# euromap.net
KiCad netlist of a schematic drawn in Altium Designer
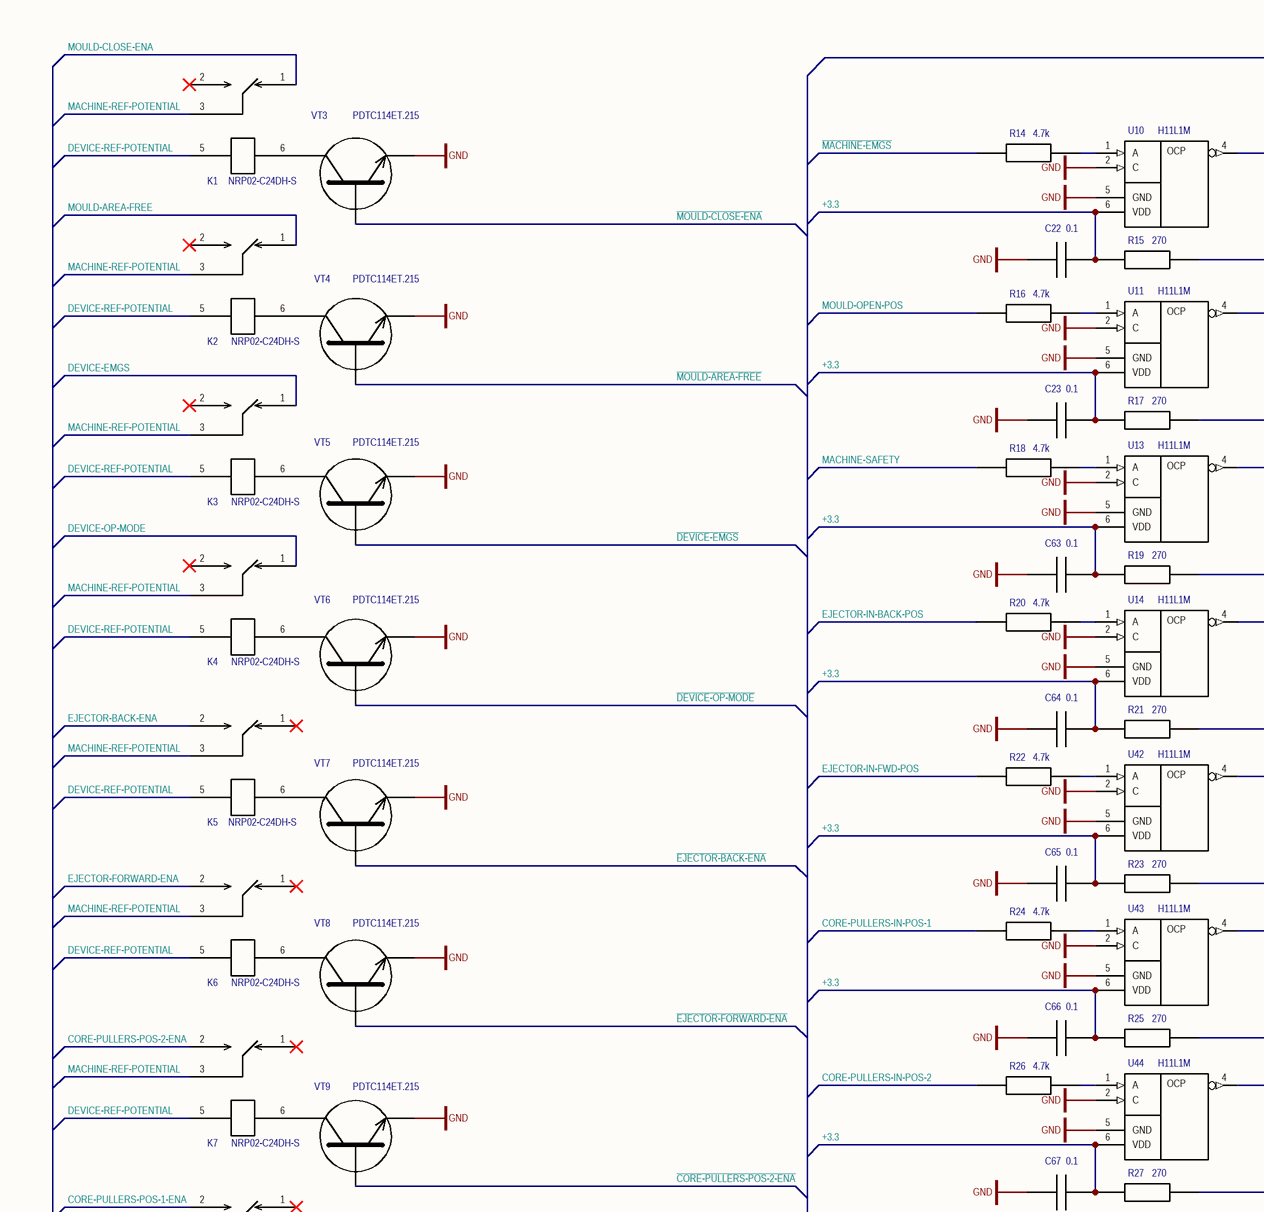
[diagram p0: euromap.SchDoc, top left]
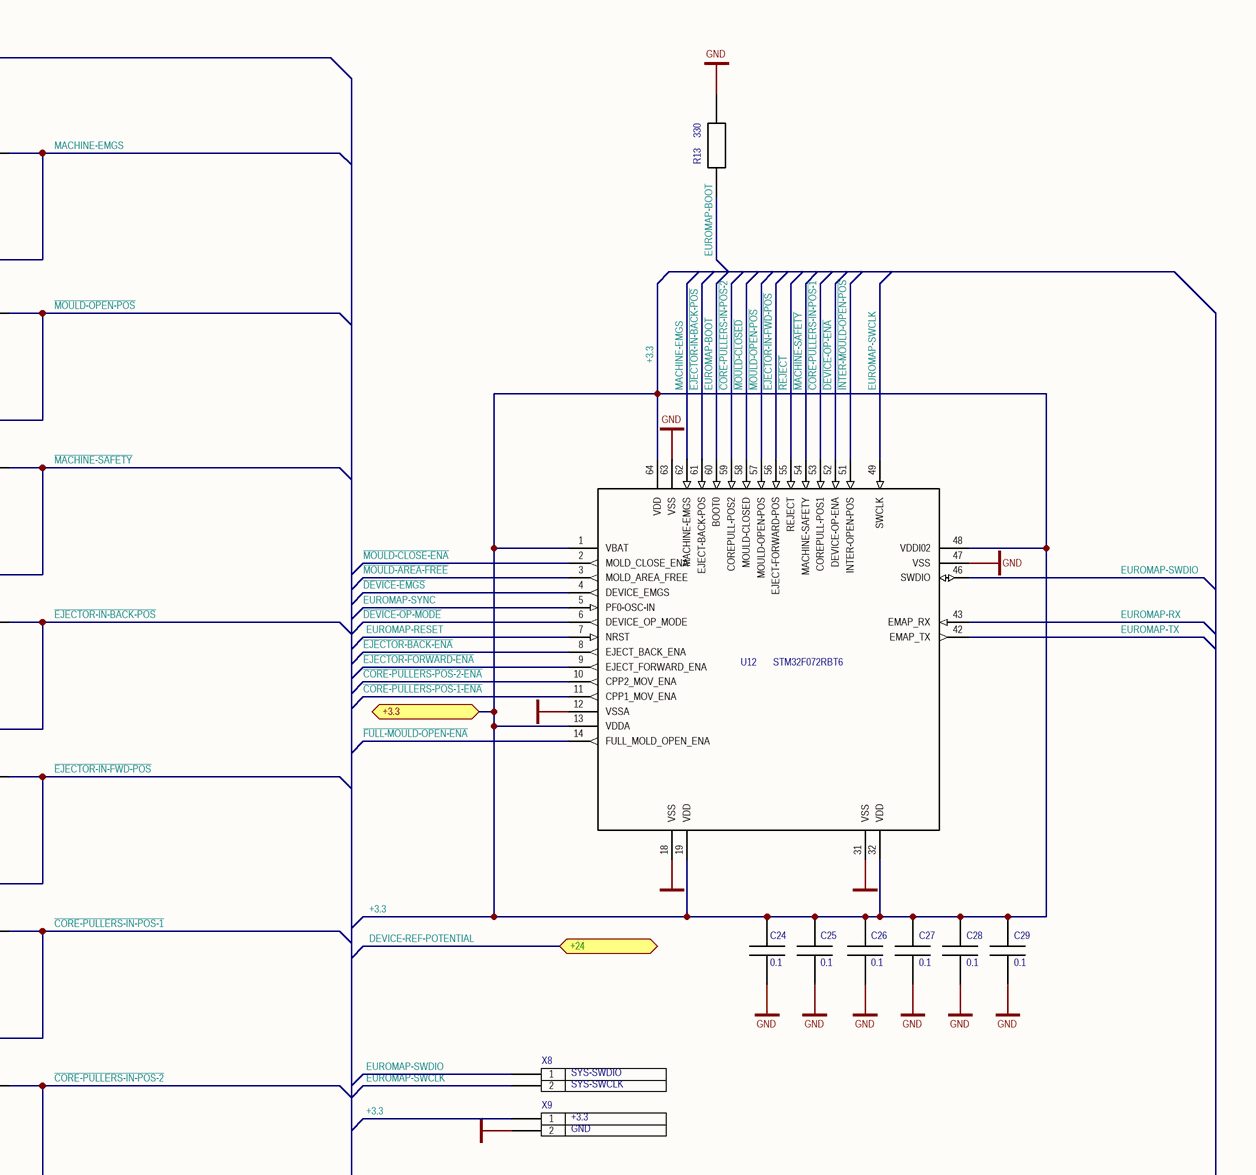
[diagram p1: euromap.SchDoc, top right]
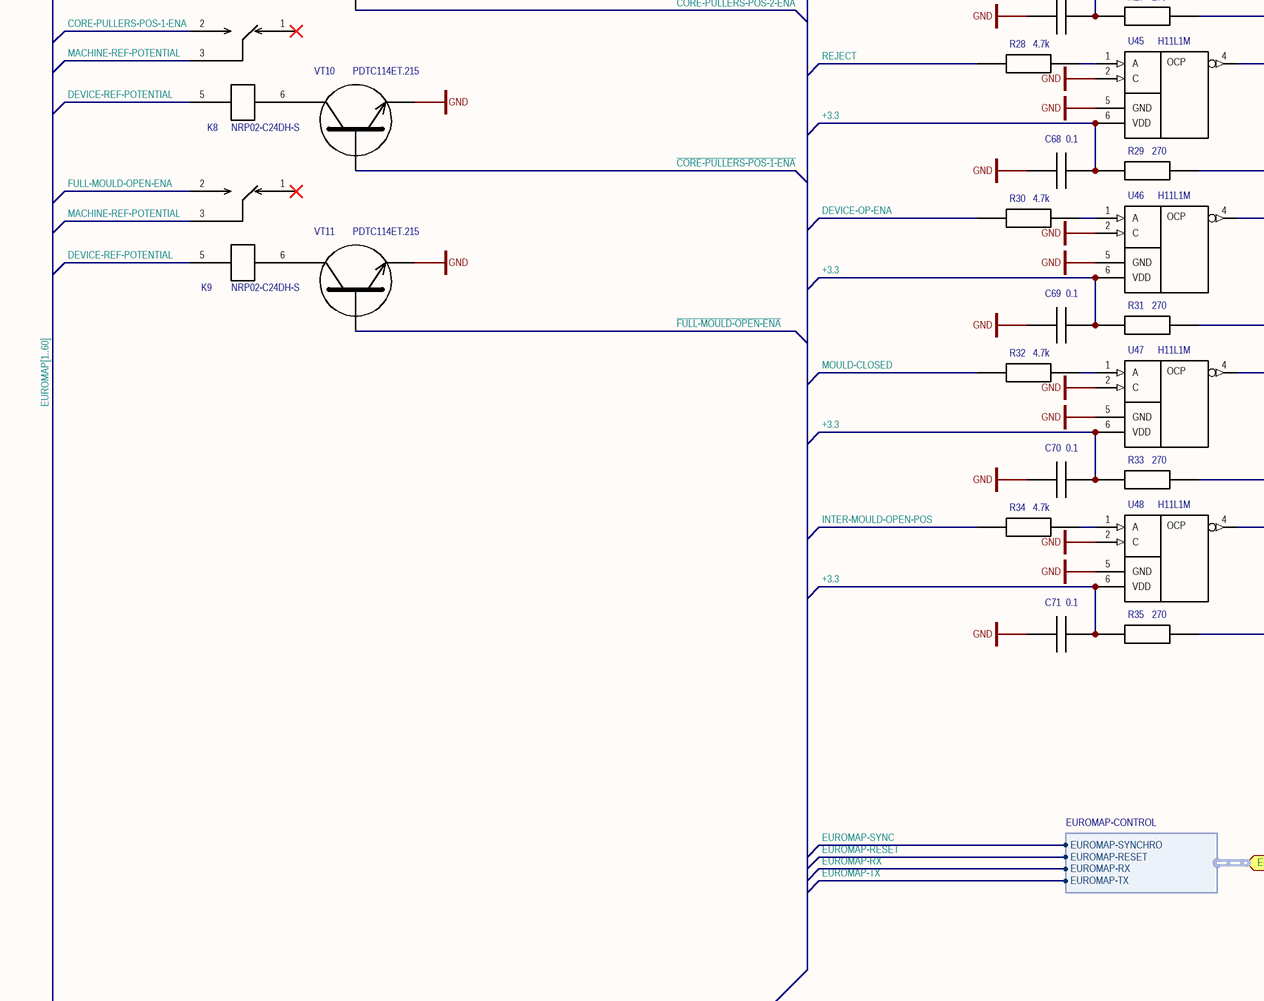
[diagram p2: euromap.SchDoc, bottom left]
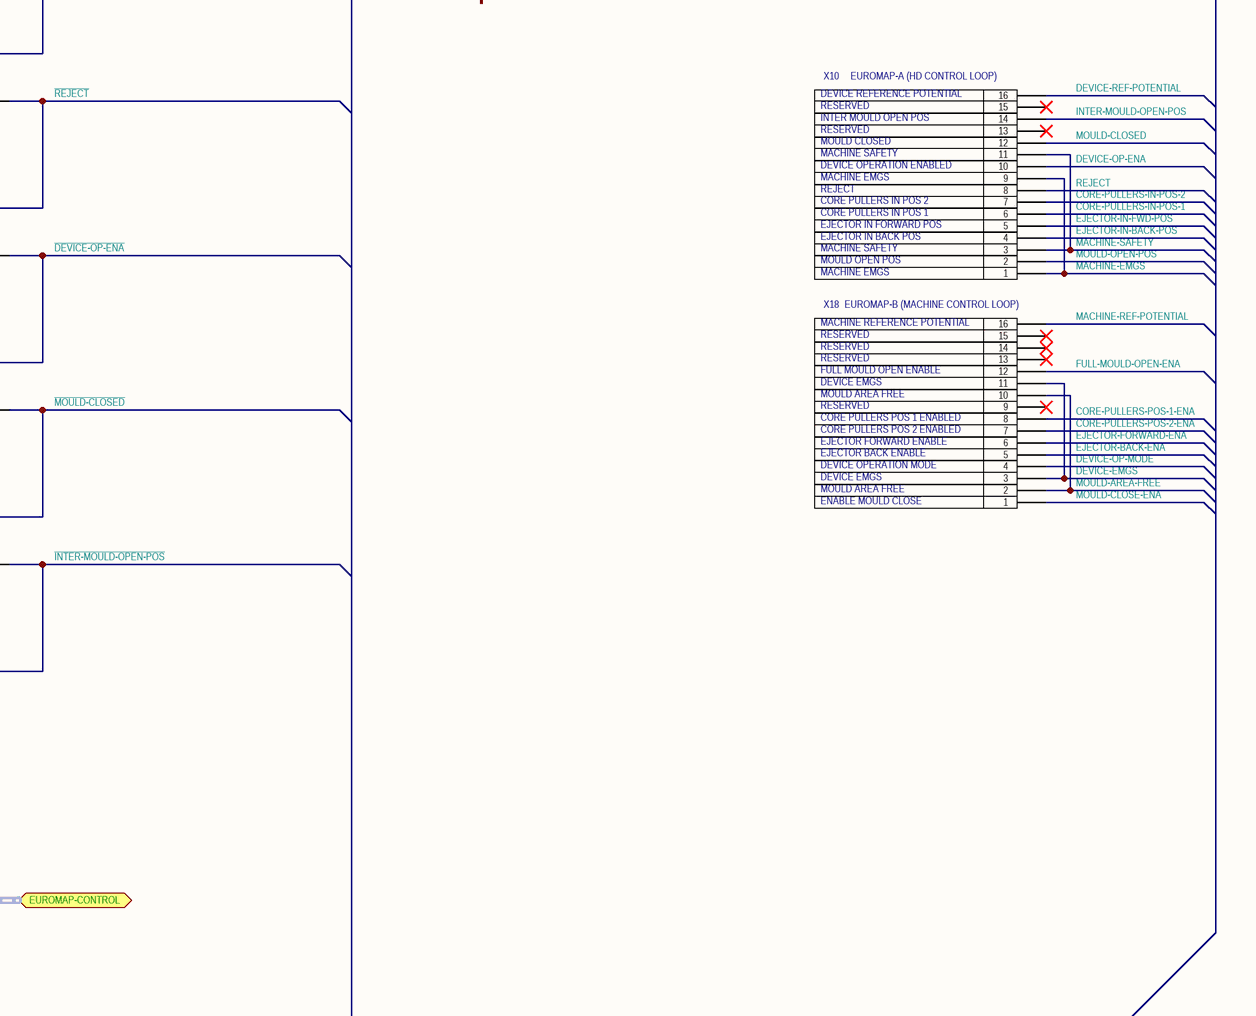
[diagram p3: euromap.SchDoc, bottom right]

(export (version "E")
  (design (tool "Eeschema 10.0.6"))
  (components
    (comp (ref "C22")
      (value "0.1")
      (footprint "CAPC2012X04N")
      (description "SMD конденсатор")
      (libsource (lib "ulysses_library") (part "C"))
    )
    (comp (ref "C23")
      (value "0.1")
      (footprint "CAPC2012X04N")
      (description "SMD конденсатор")
      (libsource (lib "ulysses_library") (part "C"))
    )
    (comp (ref "C24")
      (value "0.1")
      (footprint "CAPC1608X05N")
      (description "SMD конденсатор")
      (libsource (lib "ulysses_library") (part "C"))
    )
    (comp (ref "C25")
      (value "0.1")
      (footprint "CAPC1608X05N")
      (description "SMD конденсатор")
      (libsource (lib "ulysses_library") (part "C"))
    )
    (comp (ref "C26")
      (value "0.1")
      (footprint "CAPC1608X05N")
      (description "SMD конденсатор")
      (libsource (lib "ulysses_library") (part "C"))
    )
    (comp (ref "C27")
      (value "0.1")
      (footprint "CAPC1608X05N")
      (description "SMD конденсатор")
      (libsource (lib "ulysses_library") (part "C"))
    )
    (comp (ref "C28")
      (value "0.1")
      (footprint "CAPC1608X05N")
      (description "SMD конденсатор")
      (libsource (lib "ulysses_library") (part "C"))
    )
    (comp (ref "C29")
      (value "0.1")
      (footprint "CAPC1608X05N")
      (description "SMD конденсатор")
      (libsource (lib "ulysses_library") (part "C"))
    )
    (comp (ref "C63")
      (value "0.1")
      (footprint "CAPC2012X04N")
      (description "SMD конденсатор")
      (libsource (lib "ulysses_library") (part "C"))
    )
    (comp (ref "C64")
      (value "0.1")
      (footprint "CAPC2012X04N")
      (description "SMD конденсатор")
      (libsource (lib "ulysses_library") (part "C"))
    )
    (comp (ref "C65")
      (value "0.1")
      (footprint "CAPC2012X04N")
      (description "SMD конденсатор")
      (libsource (lib "ulysses_library") (part "C"))
    )
    (comp (ref "C66")
      (value "0.1")
      (footprint "CAPC2012X04N")
      (description "SMD конденсатор")
      (libsource (lib "ulysses_library") (part "C"))
    )
    (comp (ref "C67")
      (value "0.1")
      (footprint "CAPC2012X04N")
      (description "SMD конденсатор")
      (libsource (lib "ulysses_library") (part "C"))
    )
    (comp (ref "C68")
      (value "0.1")
      (footprint "CAPC2012X04N")
      (description "SMD конденсатор")
      (libsource (lib "ulysses_library") (part "C"))
    )
    (comp (ref "C69")
      (value "0.1")
      (footprint "CAPC2012X04N")
      (description "SMD конденсатор")
      (libsource (lib "ulysses_library") (part "C"))
    )
    (comp (ref "C70")
      (value "0.1")
      (footprint "CAPC2012X04N")
      (description "SMD конденсатор")
      (libsource (lib "ulysses_library") (part "C"))
    )
    (comp (ref "C71")
      (value "0.1")
      (footprint "CAPC2012X04N")
      (description "SMD конденсатор")
      (libsource (lib "ulysses_library") (part "C"))
    )
    (comp (ref "K1")
      (value "NRP02-C24DH-S")
      (footprint "R_NRP02")
      (description "Электромеханическое реле")
      (libsource (lib "ulysses_library") (part "NRP02-C24DH-S"))
    )
    (comp (ref "K2")
      (value "NRP02-C24DH-S")
      (footprint "R_NRP02")
      (description "Электромеханическое реле")
      (libsource (lib "ulysses_library") (part "NRP02-C24DH-S"))
    )
    (comp (ref "K3")
      (value "NRP02-C24DH-S")
      (footprint "R_NRP02")
      (description "Электромеханическое реле")
      (libsource (lib "ulysses_library") (part "NRP02-C24DH-S"))
    )
    (comp (ref "K4")
      (value "NRP02-C24DH-S")
      (footprint "R_NRP02")
      (description "Электромеханическое реле")
      (libsource (lib "ulysses_library") (part "NRP02-C24DH-S"))
    )
    (comp (ref "K5")
      (value "NRP02-C24DH-S")
      (footprint "R_NRP02")
      (description "Электромеханическое реле")
      (libsource (lib "") (part "NRP02-C24DH-S_1"))
    )
    (comp (ref "K6")
      (value "NRP02-C24DH-S")
      (footprint "R_NRP02")
      (description "Электромеханическое реле")
      (libsource (lib "ulysses_library") (part "NRP02-C24DH-S"))
    )
    (comp (ref "K7")
      (value "NRP02-C24DH-S")
      (footprint "R_NRP02")
      (description "Электромеханическое реле")
      (libsource (lib "ulysses_library") (part "NRP02-C24DH-S"))
    )
    (comp (ref "K8")
      (value "NRP02-C24DH-S")
      (footprint "R_NRP02")
      (description "Электромеханическое реле")
      (libsource (lib "ulysses_library") (part "NRP02-C24DH-S"))
    )
    (comp (ref "K9")
      (value "NRP02-C24DH-S")
      (footprint "R_NRP02")
      (description "Электромеханическое реле")
      (libsource (lib "ulysses_library") (part "NRP02-C24DH-S"))
    )
    (comp (ref "R13")
      (value "330")
      (footprint "RESC1608X05N")
      (description "SMD резистор")
      (libsource (lib "ulysses_library") (part "R"))
    )
    (comp (ref "R14")
      (value "4.7k")
      (footprint "RESC2012X04N")
      (description "SMD резистор")
      (libsource (lib "ulysses_library") (part "R"))
    )
    (comp (ref "R15")
      (value "270")
      (footprint "RESC2012X04N")
      (description "SMD резистор")
      (libsource (lib "ulysses_library") (part "R"))
    )
    (comp (ref "R16")
      (value "4.7k")
      (footprint "RESC2012X04N")
      (description "SMD резистор")
      (libsource (lib "ulysses_library") (part "R"))
    )
    (comp (ref "R17")
      (value "270")
      (footprint "RESC2012X04N")
      (description "SMD резистор")
      (libsource (lib "ulysses_library") (part "R"))
    )
    (comp (ref "R18")
      (value "4.7k")
      (footprint "RESC2012X04N")
      (description "SMD резистор")
      (libsource (lib "ulysses_library") (part "R"))
    )
    (comp (ref "R19")
      (value "270")
      (footprint "RESC2012X04N")
      (description "SMD резистор")
      (libsource (lib "ulysses_library") (part "R"))
    )
    (comp (ref "R20")
      (value "4.7k")
      (footprint "RESC2012X04N")
      (description "SMD резистор")
      (libsource (lib "ulysses_library") (part "R"))
    )
    (comp (ref "R21")
      (value "270")
      (footprint "RESC2012X04N")
      (description "SMD резистор")
      (libsource (lib "ulysses_library") (part "R"))
    )
    (comp (ref "R22")
      (value "4.7k")
      (footprint "RESC2012X04N")
      (description "SMD резистор")
      (libsource (lib "ulysses_library") (part "R"))
    )
    (comp (ref "R23")
      (value "270")
      (footprint "RESC2012X04N")
      (description "SMD резистор")
      (libsource (lib "ulysses_library") (part "R"))
    )
    (comp (ref "R24")
      (value "4.7k")
      (footprint "RESC2012X04N")
      (description "SMD резистор")
      (libsource (lib "ulysses_library") (part "R"))
    )
    (comp (ref "R25")
      (value "270")
      (footprint "RESC2012X04N")
      (description "SMD резистор")
      (libsource (lib "ulysses_library") (part "R"))
    )
    (comp (ref "R26")
      (value "4.7k")
      (footprint "RESC2012X04N")
      (description "SMD резистор")
      (libsource (lib "ulysses_library") (part "R"))
    )
    (comp (ref "R27")
      (value "270")
      (footprint "RESC2012X04N")
      (description "SMD резистор")
      (libsource (lib "ulysses_library") (part "R"))
    )
    (comp (ref "R28")
      (value "4.7k")
      (footprint "RESC2012X04N")
      (description "SMD резистор")
      (libsource (lib "ulysses_library") (part "R"))
    )
    (comp (ref "R29")
      (value "270")
      (footprint "RESC2012X04N")
      (description "SMD резистор")
      (libsource (lib "ulysses_library") (part "R"))
    )
    (comp (ref "R30")
      (value "4.7k")
      (footprint "RESC2012X04N")
      (description "SMD резистор")
      (libsource (lib "ulysses_library") (part "R"))
    )
    (comp (ref "R31")
      (value "270")
      (footprint "RESC2012X04N")
      (description "SMD резистор")
      (libsource (lib "ulysses_library") (part "R"))
    )
    (comp (ref "R32")
      (value "4.7k")
      (footprint "RESC2012X04N")
      (description "SMD резистор")
      (libsource (lib "ulysses_library") (part "R"))
    )
    (comp (ref "R33")
      (value "270")
      (footprint "RESC2012X04N")
      (description "SMD резистор")
      (libsource (lib "ulysses_library") (part "R"))
    )
    (comp (ref "R34")
      (value "4.7k")
      (footprint "RESC2012X04N")
      (description "SMD резистор")
      (libsource (lib "ulysses_library") (part "R"))
    )
    (comp (ref "R35")
      (value "270")
      (footprint "RESC2012X04N")
      (description "SMD резистор")
      (libsource (lib "ulysses_library") (part "R"))
    )
    (comp (ref "U10")
      (value "H11L1M")
      (footprint "DIP6")
      (description "Fairchild H11L1M Schmitt Trigger Output Optocoupler")
      (libsource (lib "ulysses_library") (part "H11L1M"))
    )
    (comp (ref "U11")
      (value "H11L1M")
      (footprint "DIP6")
      (description "Fairchild H11L1M Schmitt Trigger Output Optocoupler")
      (libsource (lib "ulysses_library") (part "H11L1M"))
    )
    (comp (ref "U12")
      (value "STM32F072RBT6")
      (footprint "TSQFP50P1200X1200X160-64N")
      (description "Микроконтроллер")
      (libsource (lib "ulysses_library") (part "STM32F072RBT6"))
    )
    (comp (ref "U13")
      (value "H11L1M")
      (footprint "DIP6")
      (description "Fairchild H11L1M Schmitt Trigger Output Optocoupler")
      (libsource (lib "ulysses_library") (part "H11L1M"))
    )
    (comp (ref "U14")
      (value "H11L1M")
      (footprint "DIP6")
      (description "Fairchild H11L1M Schmitt Trigger Output Optocoupler")
      (libsource (lib "ulysses_library") (part "H11L1M"))
    )
    (comp (ref "U42")
      (value "H11L1M")
      (footprint "DIP6")
      (description "Fairchild H11L1M Schmitt Trigger Output Optocoupler")
      (libsource (lib "") (part "H11L1M_1"))
    )
    (comp (ref "U43")
      (value "H11L1M")
      (footprint "DIP6")
      (description "Fairchild H11L1M Schmitt Trigger Output Optocoupler")
      (libsource (lib "ulysses_library") (part "H11L1M"))
    )
    (comp (ref "U44")
      (value "H11L1M")
      (footprint "DIP6")
      (description "Fairchild H11L1M Schmitt Trigger Output Optocoupler")
      (libsource (lib "ulysses_library") (part "H11L1M"))
    )
    (comp (ref "U45")
      (value "H11L1M")
      (footprint "DIP6")
      (description "Fairchild H11L1M Schmitt Trigger Output Optocoupler")
      (libsource (lib "ulysses_library") (part "H11L1M"))
    )
    (comp (ref "U46")
      (value "H11L1M")
      (footprint "DIP6")
      (description "Fairchild H11L1M Schmitt Trigger Output Optocoupler")
      (libsource (lib "ulysses_library") (part "H11L1M"))
    )
    (comp (ref "U47")
      (value "H11L1M")
      (footprint "DIP6")
      (description "Fairchild H11L1M Schmitt Trigger Output Optocoupler")
      (libsource (lib "ulysses_library") (part "H11L1M"))
    )
    (comp (ref "U48")
      (value "H11L1M")
      (footprint "DIP6")
      (description "Fairchild H11L1M Schmitt Trigger Output Optocoupler")
      (libsource (lib "ulysses_library") (part "H11L1M"))
    )
    (comp (ref "VT3")
      (value "PDTC114ET.215")
      (footprint "SOT95P238X102-3N")
      (description "NPN transistor with bias circuit")
      (libsource (lib "ulysses_library") (part "PDTC114ET.215"))
    )
    (comp (ref "VT4")
      (value "PDTC114ET.215")
      (footprint "SOT95P238X102-3N")
      (description "NPN transistor with bias circuit")
      (libsource (lib "ulysses_library") (part "PDTC114ET.215"))
    )
    (comp (ref "VT5")
      (value "PDTC114ET.215")
      (footprint "SOT95P238X102-3N")
      (description "NPN transistor with bias circuit")
      (libsource (lib "ulysses_library") (part "PDTC114ET.215"))
    )
    (comp (ref "VT6")
      (value "PDTC114ET.215")
      (footprint "SOT95P238X102-3N")
      (description "NPN transistor with bias circuit")
      (libsource (lib "ulysses_library") (part "PDTC114ET.215"))
    )
    (comp (ref "VT7")
      (value "PDTC114ET.215")
      (footprint "SOT95P238X102-3N")
      (description "NPN transistor with bias circuit")
      (libsource (lib "") (part "PDTC114ET.215_1"))
    )
    (comp (ref "VT8")
      (value "PDTC114ET.215")
      (footprint "SOT95P238X102-3N")
      (description "NPN transistor with bias circuit")
      (libsource (lib "ulysses_library") (part "PDTC114ET.215"))
    )
    (comp (ref "VT9")
      (value "PDTC114ET.215")
      (footprint "SOT95P238X102-3N")
      (description "NPN transistor with bias circuit")
      (libsource (lib "ulysses_library") (part "PDTC114ET.215"))
    )
    (comp (ref "VT10")
      (value "PDTC114ET.215")
      (footprint "SOT95P238X102-3N")
      (description "NPN transistor with bias circuit")
      (libsource (lib "ulysses_library") (part "PDTC114ET.215"))
    )
    (comp (ref "VT11")
      (value "PDTC114ET.215")
      (footprint "SOT95P238X102-3N")
      (description "NPN transistor with bias circuit")
      (libsource (lib "ulysses_library") (part "PDTC114ET.215"))
    )
    (comp (ref "X8")
      (value "Jamper ZL201")
      (footprint "ZL201-2")
      (libsource (lib "ulysses_library") (part "Jamper ZL201"))
    )
    (comp (ref "X9")
      (value "Jamper ZL201")
      (footprint "ZL201-2")
      (libsource (lib "ulysses_library") (part "Jamper ZL201"))
    )
    (comp (ref "X10")
      (value "EUROMAP-A (HD CONTROL LOOP)")
      (footprint "MINI-FIT-16-WAY-M")
      (libsource (lib "ulysses_library") (part "MINI-FIT-16-WAY-M"))
    )
    (comp (ref "X18")
      (value "EUROMAP-B (MACHINE CONTROL LOOP)")
      (footprint "MINI-FIT-16-WAY-M")
      (libsource (lib "ulysses_library") (part "MINI-FIT-16-WAY-M"))
    )
  )
  (nets
    (net (code "62") (name "/+3.3") (class "Default")
      (node (ref "C22") (pin "2") (pinfunction "2_2") (pintype "passive"))
      (node (ref "C23") (pin "2") (pinfunction "2_2") (pintype "passive"))
      (node (ref "C24") (pin "2") (pinfunction "2_2") (pintype "passive"))
      (node (ref "C25") (pin "2") (pinfunction "2_2") (pintype "passive"))
      (node (ref "C26") (pin "2") (pinfunction "2_2") (pintype "passive"))
      (node (ref "C27") (pin "2") (pinfunction "2_2") (pintype "passive"))
      (node (ref "C28") (pin "2") (pinfunction "2_2") (pintype "passive"))
      (node (ref "C29") (pin "2") (pinfunction "2_2") (pintype "passive"))
      (node (ref "C63") (pin "2") (pinfunction "2_2") (pintype "passive"))
      (node (ref "C64") (pin "2") (pinfunction "2_2") (pintype "passive"))
      (node (ref "C65") (pin "2") (pinfunction "2_2") (pintype "passive"))
      (node (ref "C66") (pin "2") (pinfunction "2_2") (pintype "passive"))
      (node (ref "C67") (pin "2") (pinfunction "2_2") (pintype "passive"))
      (node (ref "C68") (pin "2") (pinfunction "2_2") (pintype "passive"))
      (node (ref "C69") (pin "2") (pinfunction "2_2") (pintype "passive"))
      (node (ref "C70") (pin "2") (pinfunction "2_2") (pintype "passive"))
      (node (ref "C71") (pin "2") (pinfunction "2_2") (pintype "passive"))
      (node (ref "R15") (pin "1") (pintype "passive"))
      (node (ref "R17") (pin "1") (pintype "passive"))
      (node (ref "R19") (pin "1") (pintype "passive"))
      (node (ref "R21") (pin "1") (pintype "passive"))
      (node (ref "R23") (pin "1") (pintype "passive"))
      (node (ref "R25") (pin "1") (pintype "passive"))
      (node (ref "R27") (pin "1") (pintype "passive"))
      (node (ref "R29") (pin "1") (pintype "passive"))
      (node (ref "R31") (pin "1") (pintype "passive"))
      (node (ref "R33") (pin "1") (pintype "passive"))
      (node (ref "R35") (pin "1") (pintype "passive"))
      (node (ref "U10") (pin "6") (pinfunction "VDD_6") (pintype "power_in"))
      (node (ref "U11") (pin "6") (pinfunction "VDD_6") (pintype "power_in"))
      (node (ref "U12") (pin "1") (pinfunction "VBAT_1") (pintype "power_in"))
      (node (ref "U12") (pin "13") (pinfunction "VDDA_13") (pintype "power_in"))
      (node (ref "U12") (pin "19") (pinfunction "VDD_19") (pintype "power_in"))
      (node (ref "U12") (pin "32") (pinfunction "VDD_32") (pintype "power_in"))
      (node (ref "U12") (pin "48") (pinfunction "VDDI02_48") (pintype "power_in"))
      (node (ref "U12") (pin "64") (pinfunction "VDD_64") (pintype "power_in"))
      (node (ref "U13") (pin "6") (pinfunction "VDD_6") (pintype "power_in"))
      (node (ref "U14") (pin "6") (pinfunction "VDD_6") (pintype "power_in"))
      (node (ref "U42") (pin "6") (pinfunction "VDD_6") (pintype "power_in"))
      (node (ref "U43") (pin "6") (pinfunction "VDD_6") (pintype "power_in"))
      (node (ref "U44") (pin "6") (pinfunction "VDD_6") (pintype "power_in"))
      (node (ref "U45") (pin "6") (pinfunction "VDD_6") (pintype "power_in"))
      (node (ref "U46") (pin "6") (pinfunction "VDD_6") (pintype "power_in"))
      (node (ref "U47") (pin "6") (pinfunction "VDD_6") (pintype "power_in"))
      (node (ref "U48") (pin "6") (pinfunction "VDD_6") (pintype "power_in"))
      (node (ref "X9") (pin "1") (pinfunction "1_1") (pintype "passive"))
    )
    (net (code "63") (name "/CORE-PULLERS-IN-POS-1") (class "Default")
      (node (ref "R24") (pin "1") (pintype "passive"))
      (node (ref "X10") (pin "6") (pinfunction "6_6") (pintype "passive"))
    )
    (net (code "64") (name "/CORE-PULLERS-IN-POS-2") (class "Default")
      (node (ref "R26") (pin "1") (pintype "passive"))
      (node (ref "X10") (pin "7") (pinfunction "7_7") (pintype "passive"))
    )
    (net (code "65") (name "/CORE-PULLERS-POS-1-ENA") (class "Default")
      (node (ref "K8") (pin "2") (pinfunction "2_2") (pintype "passive"))
      (node (ref "X18") (pin "8") (pinfunction "8_8") (pintype "passive"))
    )
    (net (code "66") (name "/CORE-PULLERS-POS-2-ENA") (class "Default")
      (node (ref "K7") (pin "2") (pinfunction "2_2") (pintype "passive"))
      (node (ref "X18") (pin "7") (pinfunction "7_7") (pintype "passive"))
    )
    (net (code "67") (name "/DEVICE-EMGS") (class "Default")
      (node (ref "K3") (pin "1") (pinfunction "1_1") (pintype "passive"))
      (node (ref "X18") (pin "11") (pinfunction "11_11") (pintype "passive"))
      (node (ref "X18") (pin "3") (pinfunction "3_3") (pintype "passive"))
    )
    (net (code "68") (name "/DEVICE-OP-ENA") (class "Default")
      (node (ref "R30") (pin "1") (pintype "passive"))
      (node (ref "X10") (pin "10") (pinfunction "10_10") (pintype "passive"))
    )
    (net (code "69") (name "/DEVICE-OP-MODE") (class "Default")
      (node (ref "K4") (pin "1") (pinfunction "1_1") (pintype "passive"))
      (node (ref "X18") (pin "4") (pinfunction "4_4") (pintype "passive"))
    )
    (net (code "70") (name "/DEVICE-REF-POTENTIAL") (class "Default")
      (node (ref "K1") (pin "5") (pinfunction "5_5") (pintype "passive"))
      (node (ref "K2") (pin "5") (pinfunction "5_5") (pintype "passive"))
      (node (ref "K3") (pin "5") (pinfunction "5_5") (pintype "passive"))
      (node (ref "K4") (pin "5") (pinfunction "5_5") (pintype "passive"))
      (node (ref "K5") (pin "5") (pinfunction "5_5") (pintype "passive"))
      (node (ref "K6") (pin "5") (pinfunction "5_5") (pintype "passive"))
      (node (ref "K7") (pin "5") (pinfunction "5_5") (pintype "passive"))
      (node (ref "K8") (pin "5") (pinfunction "5_5") (pintype "passive"))
      (node (ref "K9") (pin "5") (pinfunction "5_5") (pintype "passive"))
      (node (ref "X10") (pin "16") (pinfunction "16_16") (pintype "passive"))
    )
    (net (code "71") (name "/EJECTOR-BACK-ENA") (class "Default")
      (node (ref "K5") (pin "2") (pinfunction "2_2") (pintype "passive"))
      (node (ref "X18") (pin "5") (pinfunction "5_5") (pintype "passive"))
    )
    (net (code "72") (name "/EJECTOR-FORWARD-ENA") (class "Default")
      (node (ref "K6") (pin "2") (pinfunction "2_2") (pintype "passive"))
      (node (ref "X18") (pin "6") (pinfunction "6_6") (pintype "passive"))
    )
    (net (code "73") (name "/EJECTOR-IN-BACK-POS") (class "Default")
      (node (ref "R20") (pin "1") (pintype "passive"))
      (node (ref "X10") (pin "4") (pinfunction "4_4") (pintype "passive"))
    )
    (net (code "74") (name "/EJECTOR-IN-FWD-POS") (class "Default")
      (node (ref "R22") (pin "1") (pintype "passive"))
      (node (ref "X10") (pin "5") (pinfunction "5_5") (pintype "passive"))
    )
    (net (code "75") (name "/EUROMAP-BOOT") (class "Default")
      (node (ref "R13") (pin "2") (pinfunction "2_2") (pintype "passive"))
      (node (ref "U12") (pin "60") (pinfunction "BOOT0_60") (pintype "input"))
    )
    (net (code "76") (name "/EUROMAP-RESET") (class "Default")
      (node (ref "U12") (pin "7") (pinfunction "NRST_7") (pintype "input"))
    )
    (net (code "77") (name "/EUROMAP-RX") (class "Default")
      (node (ref "U12") (pin "43") (pinfunction "EMAP_RX_43") (pintype "input"))
    )
    (net (code "78") (name "/EUROMAP-SWCLK") (class "Default")
      (node (ref "U12") (pin "49") (pinfunction "SWCLK_49") (pintype "input"))
      (node (ref "X8") (pin "2") (pinfunction "2_2") (pintype "passive"))
    )
    (net (code "79") (name "/EUROMAP-SWDIO") (class "Default")
      (node (ref "U12") (pin "46") (pinfunction "SWDIO_46") (pintype "bidirectional"))
      (node (ref "X8") (pin "1") (pinfunction "1_1") (pintype "passive"))
    )
    (net (code "80") (name "/EUROMAP-SYNC") (class "Default")
      (node (ref "U12") (pin "5") (pinfunction "PF0-OSC-IN_5") (pintype "input"))
    )
    (net (code "81") (name "/EUROMAP-TX") (class "Default")
      (node (ref "U12") (pin "42") (pinfunction "EMAP_TX_42") (pintype "output"))
    )
    (net (code "83") (name "/FULL-MOULD-OPEN-ENA") (class "Default")
      (node (ref "K9") (pin "2") (pinfunction "2_2") (pintype "passive"))
      (node (ref "X18") (pin "12") (pinfunction "12_12") (pintype "passive"))
    )
    (net (code "84") (name "/INTER-MOULD-OPEN-POS") (class "Default")
      (node (ref "R34") (pin "1") (pintype "passive"))
      (node (ref "X10") (pin "14") (pinfunction "14_14") (pintype "passive"))
    )
    (net (code "85") (name "/MACHINE-EMGS") (class "Default")
      (node (ref "R15") (pin "2") (pinfunction "2_2") (pintype "passive"))
      (node (ref "U10") (pin "4") (pinfunction "OUT_4") (pintype "output"))
      (node (ref "U12") (pin "62") (pinfunction "MACHINE-EMGS_62") (pintype "input"))
      (node (ref "X10") (pin "1") (pinfunction "1_1") (pintype "passive"))
      (node (ref "X10") (pin "9") (pinfunction "9_9") (pintype "passive"))
    )
    (net (code "86") (name "/MACHINE-REF-POTENTIAL") (class "Default")
      (node (ref "K1") (pin "3") (pinfunction "3_3") (pintype "passive"))
      (node (ref "K2") (pin "3") (pinfunction "3_3") (pintype "passive"))
      (node (ref "K3") (pin "3") (pinfunction "3_3") (pintype "passive"))
      (node (ref "K4") (pin "3") (pinfunction "3_3") (pintype "passive"))
      (node (ref "K5") (pin "3") (pinfunction "3_3") (pintype "passive"))
      (node (ref "K6") (pin "3") (pinfunction "3_3") (pintype "passive"))
      (node (ref "K7") (pin "3") (pinfunction "3_3") (pintype "passive"))
      (node (ref "K8") (pin "3") (pinfunction "3_3") (pintype "passive"))
      (node (ref "K9") (pin "3") (pinfunction "3_3") (pintype "passive"))
      (node (ref "X18") (pin "16") (pinfunction "16_16") (pintype "passive"))
    )
    (net (code "87") (name "/MACHINE-SAFETY") (class "Default")
      (node (ref "R18") (pin "1") (pintype "passive"))
      (node (ref "X10") (pin "11") (pinfunction "11_11") (pintype "passive"))
      (node (ref "X10") (pin "3") (pinfunction "3_3") (pintype "passive"))
    )
    (net (code "88") (name "/MOULD-AREA-FREE") (class "Default")
      (node (ref "K2") (pin "1") (pinfunction "1_1") (pintype "passive"))
      (node (ref "X18") (pin "10") (pinfunction "10_10") (pintype "passive"))
      (node (ref "X18") (pin "2") (pinfunction "2_2") (pintype "passive"))
    )
    (net (code "89") (name "/MOULD-CLOSE-ENA") (class "Default")
      (node (ref "K1") (pin "1") (pinfunction "1_1") (pintype "passive"))
      (node (ref "X18") (pin "1") (pinfunction "1_1") (pintype "passive"))
    )
    (net (code "90") (name "/MOULD-CLOSED") (class "Default")
      (node (ref "R32") (pin "1") (pintype "passive"))
      (node (ref "X10") (pin "12") (pinfunction "12_12") (pintype "passive"))
    )
    (net (code "91") (name "/MOULD-OPEN-POS") (class "Default")
      (node (ref "R16") (pin "1") (pintype "passive"))
      (node (ref "X10") (pin "2") (pinfunction "2_2") (pintype "passive"))
    )
    (net (code "92") (name "/REJECT") (class "Default")
      (node (ref "R28") (pin "1") (pintype "passive"))
      (node (ref "X10") (pin "8") (pinfunction "8_8") (pintype "passive"))
    )
    (net (code "94") (name "/~{CORE-PULLERS-IN-POS-1}") (class "Default")
      (node (ref "R25") (pin "2") (pinfunction "2_2") (pintype "passive"))
      (node (ref "U12") (pin "53") (pinfunction "COREPULL-POS1_53") (pintype "input"))
      (node (ref "U43") (pin "4") (pinfunction "OUT_4") (pintype "output"))
    )
    (net (code "95") (name "/~{CORE-PULLERS-IN-POS-2}") (class "Default")
      (node (ref "R27") (pin "2") (pinfunction "2_2") (pintype "passive"))
      (node (ref "U12") (pin "59") (pinfunction "COREPULL-POS2_59") (pintype "input"))
      (node (ref "U44") (pin "4") (pinfunction "OUT_4") (pintype "output"))
    )
    (net (code "96") (name "/~{CORE-PULLERS-POS-1-ENA}") (class "Default")
      (node (ref "U12") (pin "11") (pinfunction "CPP1_MOV_ENA_11") (pintype "output"))
      (node (ref "VT10") (pin "1") (pinfunction "B_1") (pintype "power_in"))
    )
    (net (code "97") (name "/~{CORE-PULLERS-POS-2-ENA}") (class "Default")
      (node (ref "U12") (pin "10") (pinfunction "CPP2_MOV_ENA_10") (pintype "output"))
      (node (ref "VT9") (pin "1") (pinfunction "B_1") (pintype "power_in"))
    )
    (net (code "98") (name "/~{DEVICE-EMGS}") (class "Default")
      (node (ref "U12") (pin "4") (pinfunction "DEVICE_EMGS_4") (pintype "output"))
      (node (ref "VT5") (pin "1") (pinfunction "B_1") (pintype "power_in"))
    )
    (net (code "99") (name "/~{DEVICE-OP-ENA}") (class "Default")
      (node (ref "R31") (pin "2") (pinfunction "2_2") (pintype "passive"))
      (node (ref "U12") (pin "52") (pinfunction "DEVICE-OP-ENA_52") (pintype "input"))
      (node (ref "U46") (pin "4") (pinfunction "OUT_4") (pintype "output"))
    )
    (net (code "100") (name "/~{DEVICE-OP-MODE}") (class "Default")
      (node (ref "U12") (pin "6") (pinfunction "DEVICE_OP_MODE_6") (pintype "output"))
      (node (ref "VT6") (pin "1") (pinfunction "B_1") (pintype "power_in"))
    )
    (net (code "101") (name "/~{EJECTOR-BACK-ENA}") (class "Default")
      (node (ref "U12") (pin "8") (pinfunction "EJECT_BACK_ENA_8") (pintype "output"))
      (node (ref "VT7") (pin "1") (pinfunction "B_1") (pintype "power_in"))
    )
    (net (code "102") (name "/~{EJECTOR-FORWARD-ENA}") (class "Default")
      (node (ref "U12") (pin "9") (pinfunction "EJECT_FORWARD_ENA_9") (pintype "output"))
      (node (ref "VT8") (pin "1") (pinfunction "B_1") (pintype "power_in"))
    )
    (net (code "103") (name "/~{EJECTOR-IN-BACK-POS}") (class "Default")
      (node (ref "R21") (pin "2") (pinfunction "2_2") (pintype "passive"))
      (node (ref "U12") (pin "61") (pinfunction "EJECT-BACK-POS_61") (pintype "input"))
      (node (ref "U14") (pin "4") (pinfunction "OUT_4") (pintype "output"))
    )
    (net (code "104") (name "/~{EJECTOR-IN-FWD-POS}") (class "Default")
      (node (ref "R23") (pin "2") (pinfunction "2_2") (pintype "passive"))
      (node (ref "U12") (pin "56") (pinfunction "EJECT-FORWARD-POS_56") (pintype "input"))
      (node (ref "U42") (pin "4") (pinfunction "OUT_4") (pintype "output"))
    )
    (net (code "105") (name "/~{FULL-MOULD-OPEN-ENA}") (class "Default")
      (node (ref "U12") (pin "14") (pinfunction "FULL_MOLD_OPEN_ENA_14") (pintype "output"))
      (node (ref "VT11") (pin "1") (pinfunction "B_1") (pintype "power_in"))
    )
    (net (code "106") (name "/~{INTER-MOULD-OPEN-POS}") (class "Default")
      (node (ref "R35") (pin "2") (pinfunction "2_2") (pintype "passive"))
      (node (ref "U12") (pin "51") (pinfunction "INTER-OPEN-POS_51") (pintype "input"))
      (node (ref "U48") (pin "4") (pinfunction "OUT_4") (pintype "output"))
    )
    (net (code "107") (name "/~{MACHINE-EMGS}") (class "Default")
      (node (ref "R14") (pin "1") (pintype "passive"))
    )
    (net (code "108") (name "/~{MACHINE-SAFETY}") (class "Default")
      (node (ref "R19") (pin "2") (pinfunction "2_2") (pintype "passive"))
      (node (ref "U12") (pin "54") (pinfunction "MACHINE-SAFETY_54") (pintype "input"))
      (node (ref "U13") (pin "4") (pinfunction "OUT_4") (pintype "output"))
    )
    (net (code "109") (name "/~{MOULD-AREA-FREE}") (class "Default")
      (node (ref "U12") (pin "3") (pinfunction "MOLD_AREA_FREE_3") (pintype "output"))
      (node (ref "VT4") (pin "1") (pinfunction "B_1") (pintype "power_in"))
    )
    (net (code "110") (name "/~{MOULD-CLOSE-ENA}") (class "Default")
      (node (ref "U12") (pin "2") (pinfunction "MOLD_CLOSE_ENA_2") (pintype "output"))
      (node (ref "VT3") (pin "1") (pinfunction "B_1") (pintype "power_in"))
    )
    (net (code "111") (name "/~{MOULD-CLOSED}") (class "Default")
      (node (ref "R33") (pin "2") (pinfunction "2_2") (pintype "passive"))
      (node (ref "U12") (pin "58") (pinfunction "MOULD-CLOSED_58") (pintype "input"))
      (node (ref "U47") (pin "4") (pinfunction "OUT_4") (pintype "output"))
    )
    (net (code "112") (name "/~{MOULD-OPEN-POS}") (class "Default")
      (node (ref "R17") (pin "2") (pinfunction "2_2") (pintype "passive"))
      (node (ref "U11") (pin "4") (pinfunction "OUT_4") (pintype "output"))
      (node (ref "U12") (pin "57") (pinfunction "MOULD-OPEN-POS_57") (pintype "input"))
    )
    (net (code "113") (name "/~{REJECT}") (class "Default")
      (node (ref "R29") (pin "2") (pinfunction "2_2") (pintype "passive"))
      (node (ref "U12") (pin "55") (pinfunction "REJECT_55") (pintype "input"))
      (node (ref "U45") (pin "4") (pinfunction "OUT_4") (pintype "output"))
    )
    (net (code "114") (name "GND") (class "Default")
      (node (ref "C22") (pin "1") (pinfunction "1_1") (pintype "passive"))
      (node (ref "C23") (pin "1") (pinfunction "1_1") (pintype "passive"))
      (node (ref "C24") (pin "1") (pinfunction "1_1") (pintype "passive"))
      (node (ref "C25") (pin "1") (pinfunction "1_1") (pintype "passive"))
      (node (ref "C26") (pin "1") (pinfunction "1_1") (pintype "passive"))
      (node (ref "C27") (pin "1") (pinfunction "1_1") (pintype "passive"))
      (node (ref "C28") (pin "1") (pinfunction "1_1") (pintype "passive"))
      (node (ref "C29") (pin "1") (pinfunction "1_1") (pintype "passive"))
      (node (ref "C63") (pin "1") (pinfunction "1_1") (pintype "passive"))
      (node (ref "C64") (pin "1") (pinfunction "1_1") (pintype "passive"))
      (node (ref "C65") (pin "1") (pinfunction "1_1") (pintype "passive"))
      (node (ref "C66") (pin "1") (pinfunction "1_1") (pintype "passive"))
      (node (ref "C67") (pin "1") (pinfunction "1_1") (pintype "passive"))
      (node (ref "C68") (pin "1") (pinfunction "1_1") (pintype "passive"))
      (node (ref "C69") (pin "1") (pinfunction "1_1") (pintype "passive"))
      (node (ref "C70") (pin "1") (pinfunction "1_1") (pintype "passive"))
      (node (ref "C71") (pin "1") (pinfunction "1_1") (pintype "passive"))
      (node (ref "R13") (pin "1") (pintype "passive"))
      (node (ref "U10") (pin "2") (pinfunction "C_2") (pintype "input"))
      (node (ref "U10") (pin "5") (pinfunction "GND_5") (pintype "power_in"))
      (node (ref "U11") (pin "2") (pinfunction "C_2") (pintype "input"))
      (node (ref "U11") (pin "5") (pinfunction "GND_5") (pintype "power_in"))
      (node (ref "U12") (pin "12") (pinfunction "VSSA_12") (pintype "power_in"))
      (node (ref "U12") (pin "18") (pinfunction "VSS_18") (pintype "power_in"))
      (node (ref "U12") (pin "31") (pinfunction "VSS_31") (pintype "power_in"))
      (node (ref "U12") (pin "47") (pinfunction "VSS_47") (pintype "power_in"))
      (node (ref "U12") (pin "63") (pinfunction "VSS_63") (pintype "power_in"))
      (node (ref "U13") (pin "2") (pinfunction "C_2") (pintype "input"))
      (node (ref "U13") (pin "5") (pinfunction "GND_5") (pintype "power_in"))
      (node (ref "U14") (pin "2") (pinfunction "C_2") (pintype "input"))
      (node (ref "U14") (pin "5") (pinfunction "GND_5") (pintype "power_in"))
      (node (ref "U42") (pin "2") (pinfunction "C_2") (pintype "input"))
      (node (ref "U42") (pin "5") (pinfunction "GND_5") (pintype "power_in"))
      (node (ref "U43") (pin "2") (pinfunction "C_2") (pintype "input"))
      (node (ref "U43") (pin "5") (pinfunction "GND_5") (pintype "power_in"))
      (node (ref "U44") (pin "2") (pinfunction "C_2") (pintype "input"))
      (node (ref "U44") (pin "5") (pinfunction "GND_5") (pintype "power_in"))
      (node (ref "U45") (pin "2") (pinfunction "C_2") (pintype "input"))
      (node (ref "U45") (pin "5") (pinfunction "GND_5") (pintype "power_in"))
      (node (ref "U46") (pin "2") (pinfunction "C_2") (pintype "input"))
      (node (ref "U46") (pin "5") (pinfunction "GND_5") (pintype "power_in"))
      (node (ref "U47") (pin "2") (pinfunction "C_2") (pintype "input"))
      (node (ref "U47") (pin "5") (pinfunction "GND_5") (pintype "power_in"))
      (node (ref "U48") (pin "2") (pinfunction "C_2") (pintype "input"))
      (node (ref "U48") (pin "5") (pinfunction "GND_5") (pintype "power_in"))
      (node (ref "VT10") (pin "2") (pinfunction "E_2") (pintype "power_in"))
      (node (ref "VT11") (pin "2") (pinfunction "E_2") (pintype "power_in"))
      (node (ref "VT3") (pin "2") (pinfunction "E_2") (pintype "power_in"))
      (node (ref "VT4") (pin "2") (pinfunction "E_2") (pintype "power_in"))
      (node (ref "VT5") (pin "2") (pinfunction "E_2") (pintype "power_in"))
      (node (ref "VT6") (pin "2") (pinfunction "E_2") (pintype "power_in"))
      (node (ref "VT7") (pin "2") (pinfunction "E_2") (pintype "power_in"))
      (node (ref "VT8") (pin "2") (pinfunction "E_2") (pintype "power_in"))
      (node (ref "VT9") (pin "2") (pinfunction "E_2") (pintype "power_in"))
      (node (ref "X9") (pin "2") (pinfunction "2_2") (pintype "passive"))
    )
    (net (code "115") (name "Net-(U10-A)") (class "Default")
      (node (ref "R14") (pin "2") (pinfunction "2_2") (pintype "passive"))
      (node (ref "U10") (pin "1") (pinfunction "A_1") (pintype "input"))
    )
    (net (code "116") (name "Net-(U11-A)") (class "Default")
      (node (ref "R16") (pin "2") (pinfunction "2_2") (pintype "passive"))
      (node (ref "U11") (pin "1") (pinfunction "A_1") (pintype "input"))
    )
    (net (code "117") (name "Net-(U13-A)") (class "Default")
      (node (ref "R18") (pin "2") (pinfunction "2_2") (pintype "passive"))
      (node (ref "U13") (pin "1") (pinfunction "A_1") (pintype "input"))
    )
    (net (code "118") (name "Net-(U14-A)") (class "Default")
      (node (ref "R20") (pin "2") (pinfunction "2_2") (pintype "passive"))
      (node (ref "U14") (pin "1") (pinfunction "A_1") (pintype "input"))
    )
    (net (code "119") (name "Net-(U42-A)") (class "Default")
      (node (ref "R22") (pin "2") (pinfunction "2_2") (pintype "passive"))
      (node (ref "U42") (pin "1") (pinfunction "A_1") (pintype "input"))
    )
    (net (code "120") (name "Net-(U43-A)") (class "Default")
      (node (ref "R24") (pin "2") (pinfunction "2_2") (pintype "passive"))
      (node (ref "U43") (pin "1") (pinfunction "A_1") (pintype "input"))
    )
    (net (code "121") (name "Net-(U44-A)") (class "Default")
      (node (ref "R26") (pin "2") (pinfunction "2_2") (pintype "passive"))
      (node (ref "U44") (pin "1") (pinfunction "A_1") (pintype "input"))
    )
    (net (code "122") (name "Net-(U45-A)") (class "Default")
      (node (ref "R28") (pin "2") (pinfunction "2_2") (pintype "passive"))
      (node (ref "U45") (pin "1") (pinfunction "A_1") (pintype "input"))
    )
    (net (code "123") (name "Net-(U46-A)") (class "Default")
      (node (ref "R30") (pin "2") (pinfunction "2_2") (pintype "passive"))
      (node (ref "U46") (pin "1") (pinfunction "A_1") (pintype "input"))
    )
    (net (code "124") (name "Net-(U47-A)") (class "Default")
      (node (ref "R32") (pin "2") (pinfunction "2_2") (pintype "passive"))
      (node (ref "U47") (pin "1") (pinfunction "A_1") (pintype "input"))
    )
    (net (code "125") (name "Net-(U48-A)") (class "Default")
      (node (ref "R34") (pin "2") (pinfunction "2_2") (pintype "passive"))
      (node (ref "U48") (pin "1") (pinfunction "A_1") (pintype "input"))
    )
    (net (code "126") (name "Net-(VT3-C)") (class "Default")
      (node (ref "K1") (pin "6") (pinfunction "6_6") (pintype "passive"))
      (node (ref "VT3") (pin "3") (pinfunction "C_3") (pintype "power_in"))
    )
    (net (code "127") (name "Net-(VT4-C)") (class "Default")
      (node (ref "K2") (pin "6") (pinfunction "6_6") (pintype "passive"))
      (node (ref "VT4") (pin "3") (pinfunction "C_3") (pintype "power_in"))
    )
    (net (code "128") (name "Net-(VT5-C)") (class "Default")
      (node (ref "K3") (pin "6") (pinfunction "6_6") (pintype "passive"))
      (node (ref "VT5") (pin "3") (pinfunction "C_3") (pintype "power_in"))
    )
    (net (code "129") (name "Net-(VT6-C)") (class "Default")
      (node (ref "K4") (pin "6") (pinfunction "6_6") (pintype "passive"))
      (node (ref "VT6") (pin "3") (pinfunction "C_3") (pintype "power_in"))
    )
    (net (code "130") (name "Net-(VT7-C)") (class "Default")
      (node (ref "K5") (pin "6") (pinfunction "6_6") (pintype "passive"))
      (node (ref "VT7") (pin "3") (pinfunction "C_3") (pintype "power_in"))
    )
    (net (code "131") (name "Net-(VT8-C)") (class "Default")
      (node (ref "K6") (pin "6") (pinfunction "6_6") (pintype "passive"))
      (node (ref "VT8") (pin "3") (pinfunction "C_3") (pintype "power_in"))
    )
    (net (code "132") (name "Net-(VT9-C)") (class "Default")
      (node (ref "K7") (pin "6") (pinfunction "6_6") (pintype "passive"))
      (node (ref "VT9") (pin "3") (pinfunction "C_3") (pintype "power_in"))
    )
    (net (code "133") (name "Net-(VT10-C)") (class "Default")
      (node (ref "K8") (pin "6") (pinfunction "6_6") (pintype "passive"))
      (node (ref "VT10") (pin "3") (pinfunction "C_3") (pintype "power_in"))
    )
    (net (code "134") (name "Net-(VT11-C)") (class "Default")
      (node (ref "K9") (pin "6") (pinfunction "6_6") (pintype "passive"))
      (node (ref "VT11") (pin "3") (pinfunction "C_3") (pintype "power_in"))
    )
    (net (code "135") (name "unconnected-(K1-Pad2)") (class "Default")
      (node (ref "K1") (pin "2") (pinfunction "2_2") (pintype "passive+no_connect"))
    )
    (net (code "136") (name "unconnected-(K2-Pad2)") (class "Default")
      (node (ref "K2") (pin "2") (pinfunction "2_2") (pintype "passive+no_connect"))
    )
    (net (code "137") (name "unconnected-(K3-Pad2)") (class "Default")
      (node (ref "K3") (pin "2") (pinfunction "2_2") (pintype "passive+no_connect"))
    )
    (net (code "138") (name "unconnected-(K4-Pad2)") (class "Default")
      (node (ref "K4") (pin "2") (pinfunction "2_2") (pintype "passive+no_connect"))
    )
    (net (code "139") (name "unconnected-(K5-Pad1)") (class "Default")
      (node (ref "K5") (pin "1") (pinfunction "1_1") (pintype "passive+no_connect"))
    )
    (net (code "140") (name "unconnected-(K6-Pad1)") (class "Default")
      (node (ref "K6") (pin "1") (pinfunction "1_1") (pintype "passive+no_connect"))
    )
    (net (code "141") (name "unconnected-(K7-Pad1)") (class "Default")
      (node (ref "K7") (pin "1") (pinfunction "1_1") (pintype "passive+no_connect"))
    )
    (net (code "142") (name "unconnected-(K8-Pad1)") (class "Default")
      (node (ref "K8") (pin "1") (pinfunction "1_1") (pintype "passive+no_connect"))
    )
    (net (code "143") (name "unconnected-(K9-Pad1)") (class "Default")
      (node (ref "K9") (pin "1") (pinfunction "1_1") (pintype "passive+no_connect"))
    )
    (net (code "144") (name "unconnected-(U12-PA1-Pad15)") (class "Default")
      (node (ref "U12") (pin "15") (pinfunction "PA1_15") (pintype "passive"))
    )
    (net (code "145") (name "unconnected-(U12-PA2-Pad16)") (class "Default")
      (node (ref "U12") (pin "16") (pinfunction "PA2_16") (pintype "passive"))
    )
    (net (code "146") (name "unconnected-(U12-PA3-Pad17)") (class "Default")
      (node (ref "U12") (pin "17") (pinfunction "PA3_17") (pintype "passive"))
    )
    (net (code "147") (name "unconnected-(U12-PA4-Pad20)") (class "Default")
      (node (ref "U12") (pin "20") (pinfunction "PA4_20") (pintype "passive"))
    )
    (net (code "148") (name "unconnected-(U12-PA5-Pad21)") (class "Default")
      (node (ref "U12") (pin "21") (pinfunction "PA5_21") (pintype "passive"))
    )
    (net (code "149") (name "unconnected-(U12-PA6-Pad22)") (class "Default")
      (node (ref "U12") (pin "22") (pinfunction "PA6_22") (pintype "passive"))
    )
    (net (code "150") (name "unconnected-(U12-PA7-Pad23)") (class "Default")
      (node (ref "U12") (pin "23") (pinfunction "PA7_23") (pintype "passive"))
    )
    (net (code "151") (name "unconnected-(U12-PA8-Pad41)") (class "Default")
      (node (ref "U12") (pin "41") (pinfunction "PA8_41") (pintype "passive"))
    )
    (net (code "152") (name "unconnected-(U12-PA11-Pad44)") (class "Default")
      (node (ref "U12") (pin "44") (pinfunction "PA11_44") (pintype "passive"))
    )
    (net (code "153") (name "unconnected-(U12-PA12-Pad45)") (class "Default")
      (node (ref "U12") (pin "45") (pinfunction "PA12_45") (pintype "passive"))
    )
    (net (code "154") (name "unconnected-(U12-PA15-Pad50)") (class "Default")
      (node (ref "U12") (pin "50") (pinfunction "PA15_50") (pintype "passive"))
    )
    (net (code "155") (name "unconnected-(U12-PB0-Pad26)") (class "Default")
      (node (ref "U12") (pin "26") (pinfunction "PB0_26") (pintype "passive"))
    )
    (net (code "156") (name "unconnected-(U12-PB1-Pad27)") (class "Default")
      (node (ref "U12") (pin "27") (pinfunction "PB1_27") (pintype "passive"))
    )
    (net (code "157") (name "unconnected-(U12-PB2-Pad28)") (class "Default")
      (node (ref "U12") (pin "28") (pinfunction "PB2_28") (pintype "passive"))
    )
    (net (code "158") (name "unconnected-(U12-PB10-Pad29)") (class "Default")
      (node (ref "U12") (pin "29") (pinfunction "PB10_29") (pintype "passive"))
    )
    (net (code "159") (name "unconnected-(U12-PB11-Pad30)") (class "Default")
      (node (ref "U12") (pin "30") (pinfunction "PB11_30") (pintype "passive"))
    )
    (net (code "160") (name "unconnected-(U12-PB12-Pad33)") (class "Default")
      (node (ref "U12") (pin "33") (pinfunction "PB12_33") (pintype "passive"))
    )
    (net (code "161") (name "unconnected-(U12-PB13-Pad34)") (class "Default")
      (node (ref "U12") (pin "34") (pinfunction "PB13_34") (pintype "passive"))
    )
    (net (code "162") (name "unconnected-(U12-PB14-Pad35)") (class "Default")
      (node (ref "U12") (pin "35") (pinfunction "PB14_35") (pintype "passive"))
    )
    (net (code "163") (name "unconnected-(U12-PB15-Pad36)") (class "Default")
      (node (ref "U12") (pin "36") (pinfunction "PB15_36") (pintype "passive"))
    )
    (net (code "164") (name "unconnected-(U12-PC4-Pad24)") (class "Default")
      (node (ref "U12") (pin "24") (pinfunction "PC4_24") (pintype "passive"))
    )
    (net (code "165") (name "unconnected-(U12-PC5-Pad25)") (class "Default")
      (node (ref "U12") (pin "25") (pinfunction "PC5_25") (pintype "passive"))
    )
    (net (code "166") (name "unconnected-(U12-PC6-Pad37)") (class "Default")
      (node (ref "U12") (pin "37") (pinfunction "PC6_37") (pintype "passive"))
    )
    (net (code "167") (name "unconnected-(U12-PC7-Pad38)") (class "Default")
      (node (ref "U12") (pin "38") (pinfunction "PC7_38") (pintype "passive"))
    )
    (net (code "168") (name "unconnected-(U12-PC8-Pad39)") (class "Default")
      (node (ref "U12") (pin "39") (pinfunction "PC8_39") (pintype "passive"))
    )
    (net (code "169") (name "unconnected-(U12-PC9-Pad40)") (class "Default")
      (node (ref "U12") (pin "40") (pinfunction "PC9_40") (pintype "passive"))
    )
    (net (code "170") (name "unconnected-(X10-Pad13)") (class "Default")
      (node (ref "X10") (pin "13") (pinfunction "13_13") (pintype "passive+no_connect"))
    )
    (net (code "171") (name "unconnected-(X10-Pad15)") (class "Default")
      (node (ref "X10") (pin "15") (pinfunction "15_15") (pintype "passive+no_connect"))
    )
    (net (code "172") (name "unconnected-(X18-Pad9)") (class "Default")
      (node (ref "X18") (pin "9") (pinfunction "9_9") (pintype "passive+no_connect"))
    )
    (net (code "173") (name "unconnected-(X18-Pad13)") (class "Default")
      (node (ref "X18") (pin "13") (pinfunction "13_13") (pintype "passive+no_connect"))
    )
    (net (code "174") (name "unconnected-(X18-Pad14)") (class "Default")
      (node (ref "X18") (pin "14") (pinfunction "14_14") (pintype "passive+no_connect"))
    )
    (net (code "175") (name "unconnected-(X18-Pad15)") (class "Default")
      (node (ref "X18") (pin "15") (pinfunction "15_15") (pintype "passive+no_connect"))
    )
  )
)
